# floor.net
KiCad netlist of a schematic drawn in EAGLE
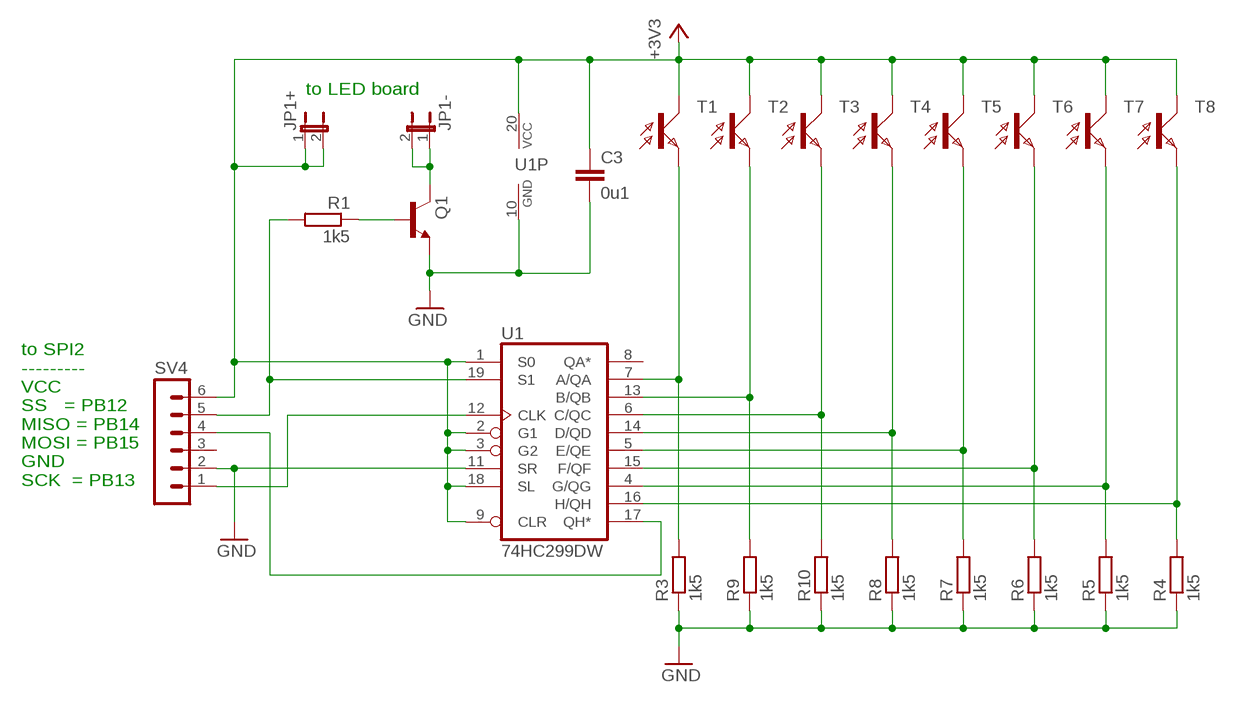
[diagram p0: schematic, sheet 1]

(export (version "E")
  (design (tool "Eeschema 10.0.6"))
  (components
    (comp (ref "C3")
      (value "0u1")
      (footprint "eagle-import:C0805")
      (libsource (lib "eagle-import") (part "C-EUC0805"))
    )
    (comp (ref "JP1+")
      (value "JP1E")
      (footprint "eagle-import:JP1")
      (libsource (lib "eagle-import") (part "JP1E"))
    )
    (comp (ref "JP1-")
      (value "JP1E")
      (footprint "eagle-import:JP1")
      (libsource (lib "eagle-import") (part "JP1E"))
    )
    (comp (ref "Q1")
      (value "BC817-25SMD")
      (footprint "eagle-import:SOT23-BEC")
      (libsource (lib "eagle-import") (part "BC817SMD-25"))
    )
    (comp (ref "R1")
      (value "1k5")
      (footprint "eagle-import:M0805")
      (libsource (lib "eagle-import") (part "R-EU_M0805"))
    )
    (comp (ref "R3")
      (value "1k5")
      (footprint "eagle-import:M0805")
      (libsource (lib "eagle-import") (part "R-EU_M0805"))
    )
    (comp (ref "R4")
      (value "1k5")
      (footprint "eagle-import:M0805")
      (libsource (lib "eagle-import") (part "R-EU_M0805"))
    )
    (comp (ref "R5")
      (value "1k5")
      (footprint "eagle-import:M0805")
      (libsource (lib "eagle-import") (part "R-EU_M0805"))
    )
    (comp (ref "R6")
      (value "1k5")
      (footprint "eagle-import:M0805")
      (libsource (lib "eagle-import") (part "R-EU_M0805"))
    )
    (comp (ref "R7")
      (value "1k5")
      (footprint "eagle-import:M0805")
      (libsource (lib "eagle-import") (part "R-EU_M0805"))
    )
    (comp (ref "R8")
      (value "1k5")
      (footprint "eagle-import:M0805")
      (libsource (lib "eagle-import") (part "R-EU_M0805"))
    )
    (comp (ref "R9")
      (value "1k5")
      (footprint "eagle-import:M0805")
      (libsource (lib "eagle-import") (part "R-EU_M0805"))
    )
    (comp (ref "R10")
      (value "1k5")
      (footprint "eagle-import:M0805")
      (libsource (lib "eagle-import") (part "R-EU_M0805"))
    )
    (comp (ref "SV4")
      (value "MA06-1")
      (footprint "eagle-import:MA06-1")
      (libsource (lib "eagle-import") (part "MA06-1"))
    )
    (comp (ref "T1")
      (value "PT17-21B")
      (footprint "eagle-import:CHIPLED_0805")
      (libsource (lib "eagle-import") (part "PHOTOTRANSISTOR"))
    )
    (comp (ref "T2")
      (value "PT17-21B")
      (footprint "eagle-import:CHIPLED_0805")
      (libsource (lib "eagle-import") (part "PHOTOTRANSISTOR"))
    )
    (comp (ref "T3")
      (value "PT17-21B")
      (footprint "eagle-import:CHIPLED_0805")
      (libsource (lib "eagle-import") (part "PHOTOTRANSISTOR"))
    )
    (comp (ref "T4")
      (value "PT17-21B")
      (footprint "eagle-import:CHIPLED_0805")
      (libsource (lib "eagle-import") (part "PHOTOTRANSISTOR"))
    )
    (comp (ref "T5")
      (value "PT17-21B")
      (footprint "eagle-import:CHIPLED_0805")
      (libsource (lib "eagle-import") (part "PHOTOTRANSISTOR"))
    )
    (comp (ref "T6")
      (value "PT17-21B")
      (footprint "eagle-import:CHIPLED_0805")
      (libsource (lib "eagle-import") (part "PHOTOTRANSISTOR"))
    )
    (comp (ref "T7")
      (value "PT17-21B")
      (footprint "eagle-import:CHIPLED_0805")
      (libsource (lib "eagle-import") (part "PHOTOTRANSISTOR"))
    )
    (comp (ref "T8")
      (value "PT17-21B")
      (footprint "eagle-import:CHIPLED_0805")
      (libsource (lib "eagle-import") (part "PHOTOTRANSISTOR"))
    )
    (comp (ref "U1")
      (value "74HC299DW")
      (footprint "eagle-import:SO20W")
      (libsource (lib "eagle-import") (part "74299DWHC"))
    )
  )
  (nets
    (net (code "1") (name "+3V3") (class "Default")
      (node (ref "C3") (pin "1") (pinfunction "1_1") (pintype "passive"))
      (node (ref "JP1+") (pin "1") (pinfunction "1_1") (pintype "passive"))
      (node (ref "JP1+") (pin "2") (pinfunction "2_2") (pintype "passive"))
      (node (ref "SV4") (pin "6") (pinfunction "6_6") (pintype "passive"))
      (node (ref "T1") (pin "C") (pinfunction "C_C") (pintype "passive"))
      (node (ref "T2") (pin "C") (pinfunction "C_C") (pintype "passive"))
      (node (ref "T3") (pin "C") (pinfunction "C_C") (pintype "passive"))
      (node (ref "T4") (pin "C") (pinfunction "C_C") (pintype "passive"))
      (node (ref "T5") (pin "C") (pinfunction "C_C") (pintype "passive"))
      (node (ref "T6") (pin "C") (pinfunction "C_C") (pintype "passive"))
      (node (ref "T7") (pin "C") (pinfunction "C_C") (pintype "passive"))
      (node (ref "T8") (pin "C") (pinfunction "C_C") (pintype "passive"))
      (node (ref "U1") (pin "1") (pinfunction "S0_1") (pintype "input"))
      (node (ref "U1") (pin "18") (pinfunction "SL_18") (pintype "input"))
      (node (ref "U1") (pin "2") (pinfunction "G1_2") (pintype "input"))
      (node (ref "U1") (pin "20") (pinfunction "VCC_20") (pintype "power_in"))
      (node (ref "U1") (pin "3") (pinfunction "G2_3") (pintype "input"))
      (node (ref "U1") (pin "9") (pinfunction "CLR_9") (pintype "input"))
    )
    (net (code "2") (name "GND") (class "Default")
      (node (ref "C3") (pin "2") (pinfunction "2_2") (pintype "passive"))
      (node (ref "Q1") (pin "E") (pinfunction "E_E") (pintype "passive"))
      (node (ref "R10") (pin "1") (pinfunction "1_1") (pintype "passive"))
      (node (ref "R3") (pin "1") (pinfunction "1_1") (pintype "passive"))
      (node (ref "R4") (pin "1") (pinfunction "1_1") (pintype "passive"))
      (node (ref "R5") (pin "1") (pinfunction "1_1") (pintype "passive"))
      (node (ref "R6") (pin "1") (pinfunction "1_1") (pintype "passive"))
      (node (ref "R7") (pin "1") (pinfunction "1_1") (pintype "passive"))
      (node (ref "R8") (pin "1") (pinfunction "1_1") (pintype "passive"))
      (node (ref "R9") (pin "1") (pinfunction "1_1") (pintype "passive"))
      (node (ref "SV4") (pin "2") (pinfunction "2_2") (pintype "passive"))
      (node (ref "U1") (pin "10") (pinfunction "GND_10") (pintype "power_in"))
      (node (ref "U1") (pin "11") (pinfunction "SR_11") (pintype "input"))
    )
    (net (code "3") (name "Net-(JP1--Pad1)") (class "Default")
      (node (ref "JP1-") (pin "1") (pinfunction "1_1") (pintype "passive"))
      (node (ref "JP1-") (pin "2") (pinfunction "2_2") (pintype "passive"))
      (node (ref "Q1") (pin "C") (pinfunction "C_C") (pintype "passive"))
    )
    (net (code "4") (name "Net-(Q1-PadB)") (class "Default")
      (node (ref "Q1") (pin "B") (pinfunction "B_B") (pintype "passive"))
      (node (ref "R1") (pin "1") (pinfunction "1_1") (pintype "passive"))
    )
    (net (code "5") (name "Net-(T1-E)") (class "Default")
      (node (ref "R3") (pin "2") (pinfunction "2_2") (pintype "passive"))
      (node (ref "T1") (pin "A") (pinfunction "E_A") (pintype "passive"))
      (node (ref "U1") (pin "7") (pinfunction "A/QA_7") (pintype "bidirectional"))
    )
    (net (code "6") (name "Net-(T2-E)") (class "Default")
      (node (ref "R9") (pin "2") (pinfunction "2_2") (pintype "passive"))
      (node (ref "T2") (pin "A") (pinfunction "E_A") (pintype "passive"))
      (node (ref "U1") (pin "13") (pinfunction "B/QB_13") (pintype "bidirectional"))
    )
    (net (code "7") (name "Net-(T3-E)") (class "Default")
      (node (ref "R10") (pin "2") (pinfunction "2_2") (pintype "passive"))
      (node (ref "T3") (pin "A") (pinfunction "E_A") (pintype "passive"))
      (node (ref "U1") (pin "6") (pinfunction "C/QC_6") (pintype "bidirectional"))
    )
    (net (code "8") (name "Net-(T4-E)") (class "Default")
      (node (ref "R8") (pin "2") (pinfunction "2_2") (pintype "passive"))
      (node (ref "T4") (pin "A") (pinfunction "E_A") (pintype "passive"))
      (node (ref "U1") (pin "14") (pinfunction "D/QD_14") (pintype "bidirectional"))
    )
    (net (code "9") (name "Net-(T5-E)") (class "Default")
      (node (ref "R7") (pin "2") (pinfunction "2_2") (pintype "passive"))
      (node (ref "T5") (pin "A") (pinfunction "E_A") (pintype "passive"))
      (node (ref "U1") (pin "5") (pinfunction "E/QE_5") (pintype "bidirectional"))
    )
    (net (code "10") (name "Net-(T6-E)") (class "Default")
      (node (ref "R6") (pin "2") (pinfunction "2_2") (pintype "passive"))
      (node (ref "T6") (pin "A") (pinfunction "E_A") (pintype "passive"))
      (node (ref "U1") (pin "15") (pinfunction "F/QF_15") (pintype "bidirectional"))
    )
    (net (code "11") (name "Net-(T7-E)") (class "Default")
      (node (ref "R5") (pin "2") (pinfunction "2_2") (pintype "passive"))
      (node (ref "T7") (pin "A") (pinfunction "E_A") (pintype "passive"))
      (node (ref "U1") (pin "4") (pinfunction "G/QG_4") (pintype "bidirectional"))
    )
    (net (code "12") (name "Net-(T8-E)") (class "Default")
      (node (ref "R4") (pin "2") (pinfunction "2_2") (pintype "passive"))
      (node (ref "T8") (pin "A") (pinfunction "E_A") (pintype "passive"))
      (node (ref "U1") (pin "16") (pinfunction "H/QH_16") (pintype "bidirectional"))
    )
    (net (code "13") (name "Net-(U1A-CLK)") (class "Default")
      (node (ref "SV4") (pin "1") (pinfunction "1_1") (pintype "passive"))
      (node (ref "U1") (pin "12") (pinfunction "CLK_12") (pintype "input"))
    )
    (net (code "14") (name "Net-(U1A-QH*)") (class "Default")
      (node (ref "SV4") (pin "4") (pinfunction "4_4") (pintype "passive"))
      (node (ref "U1") (pin "17") (pinfunction "QH*_17") (pintype "output"))
    )
    (net (code "15") (name "Net-(U1A-S1)") (class "Default")
      (node (ref "R1") (pin "2") (pinfunction "2_2") (pintype "passive"))
      (node (ref "SV4") (pin "5") (pinfunction "5_5") (pintype "passive"))
      (node (ref "U1") (pin "19") (pinfunction "S1_19") (pintype "input"))
    )
    (net (code "16") (name "unconnected-(SV4-Pad3)") (class "Default")
      (node (ref "SV4") (pin "3") (pinfunction "3_3") (pintype "passive"))
    )
    (net (code "17") (name "unconnected-(U1A-QA*-Pad8)") (class "Default")
      (node (ref "U1") (pin "8") (pinfunction "QA*_8") (pintype "output"))
    )
  )
)
